# schematic.net
KiCad netlist of a schematic drawn in EAGLE
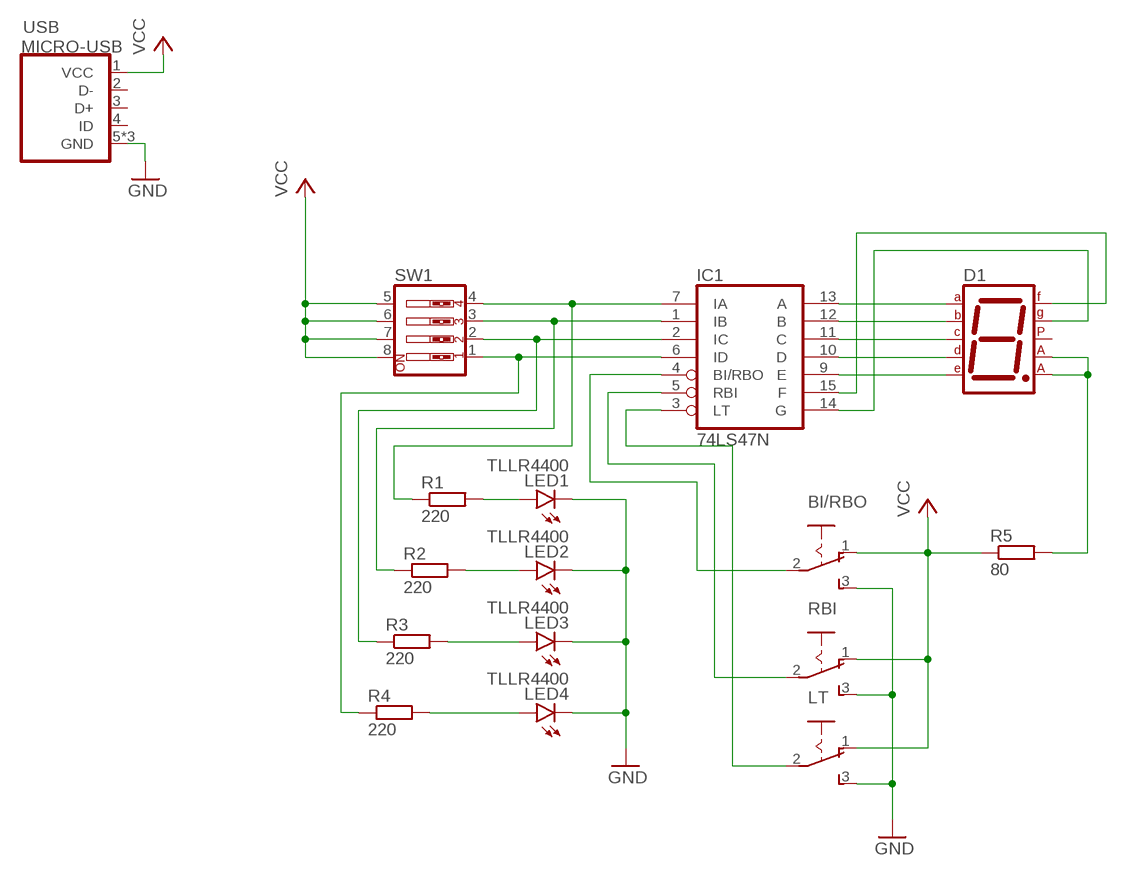
[diagram p0: schematic, sheet 1]

(export (version "E")
  (design (tool "Eeschema 10.0.6"))
  (components
    (comp (ref "BI/RBO")
      (value "255SB")
      (footprint "eagle-import:255SB")
      (libsource (lib "eagle-import") (part "255SB"))
    )
    (comp (ref "D1")
      (value "7SEG-CA")
      (footprint "eagle-import:7SEG-13")
      (libsource (lib "eagle-import") (part "7SEG-CA"))
    )
    (comp (ref "IC1")
      (value "74LS47N")
      (footprint "eagle-import:DIL16")
      (libsource (lib "eagle-import") (part "7447NLS"))
    )
    (comp (ref "LED1")
      (value "TLLR4400")
      (footprint "eagle-import:LED3MM")
      (fields (field (name "MF") "VISHAY SEMICONDUCTOR"))
      (libsource (lib "eagle-import") (part "TLLR4400"))
    )
    (comp (ref "LED2")
      (value "TLLR4400")
      (footprint "eagle-import:LED3MM")
      (fields (field (name "MF") "VISHAY SEMICONDUCTOR"))
      (libsource (lib "eagle-import") (part "TLLR4400"))
    )
    (comp (ref "LED3")
      (value "TLLR4400")
      (footprint "eagle-import:LED3MM")
      (fields (field (name "MF") "VISHAY SEMICONDUCTOR"))
      (libsource (lib "eagle-import") (part "TLLR4400"))
    )
    (comp (ref "LED4")
      (value "TLLR4400")
      (footprint "eagle-import:LED3MM")
      (fields (field (name "MF") "VISHAY SEMICONDUCTOR"))
      (libsource (lib "eagle-import") (part "TLLR4400"))
    )
    (comp (ref "LT")
      (value "255SB")
      (footprint "eagle-import:255SB")
      (libsource (lib "eagle-import") (part "255SB"))
    )
    (comp (ref "R1")
      (value "220")
      (footprint "eagle-import:0207_10")
      (libsource (lib "eagle-import") (part "R-EU_0207/10"))
    )
    (comp (ref "R2")
      (value "220")
      (footprint "eagle-import:0207_10")
      (libsource (lib "eagle-import") (part "R-EU_0207/10"))
    )
    (comp (ref "R3")
      (value "220")
      (footprint "eagle-import:0207_10")
      (libsource (lib "eagle-import") (part "R-EU_0207/10"))
    )
    (comp (ref "R4")
      (value "220")
      (footprint "eagle-import:0207_10")
      (libsource (lib "eagle-import") (part "R-EU_0207/10"))
    )
    (comp (ref "R5")
      (value "80")
      (footprint "eagle-import:0207_10")
      (libsource (lib "eagle-import") (part "R-EU_0207/10"))
    )
    (comp (ref "RBI")
      (value "255SB")
      (footprint "eagle-import:255SB")
      (libsource (lib "eagle-import") (part "255SB"))
    )
    (comp (ref "SW1")
      (value "SW_DIP-4")
      (footprint "eagle-import:EDG-04")
      (libsource (lib "eagle-import") (part "SW_DIP-4"))
    )
    (comp (ref "USB")
      (value "MICRO-USB")
      (footprint "eagle-import:MICRO-USB")
      (libsource (lib "eagle-import") (part "MICRO-USB"))
    )
  )
  (nets
    (net (code "1") (name "GND") (class "Default")
      (node (ref "BI/RBO") (pin "3") (pinfunction "S_3") (pintype "passive"))
      (node (ref "LED1") (pin "K") (pinfunction "C_K") (pintype "passive"))
      (node (ref "LED2") (pin "K") (pinfunction "C_K") (pintype "passive"))
      (node (ref "LED3") (pin "K") (pinfunction "C_K") (pintype "passive"))
      (node (ref "LED4") (pin "K") (pinfunction "C_K") (pintype "passive"))
      (node (ref "LT") (pin "3") (pinfunction "S_3") (pintype "passive"))
      (node (ref "RBI") (pin "3") (pinfunction "S_3") (pintype "passive"))
      (node (ref "USB") (pin "5") (pinfunction "GND_5") (pintype "power_in"))
      (node (ref "USB") (pin "GND1") (pinfunction "GND_GND1") (pintype "power_in"))
      (node (ref "USB") (pin "GND2") (pinfunction "GND_GND2") (pintype "power_in"))
    )
    (net (code "2") (name "Net-(BI/RBO-P)") (class "Default")
      (node (ref "BI/RBO") (pin "2") (pinfunction "P_2") (pintype "passive"))
      (node (ref "IC1") (pin "4") (pinfunction "BI/RBO_4") (pintype "input"))
    )
    (net (code "3") (name "Net-(D1-A)") (class "Default")
      (node (ref "D1") (pin "7") (pinfunction "A_7") (pintype "passive"))
      (node (ref "IC1") (pin "13") (pinfunction "A_13") (pintype "output"))
    )
    (net (code "4") (name "Net-(D1-B)") (class "Default")
      (node (ref "D1") (pin "6") (pinfunction "B_6") (pintype "passive"))
      (node (ref "IC1") (pin "12") (pinfunction "B_12") (pintype "output"))
    )
    (net (code "5") (name "Net-(D1-C)") (class "Default")
      (node (ref "D1") (pin "4") (pinfunction "C_4") (pintype "passive"))
      (node (ref "IC1") (pin "11") (pinfunction "C_11") (pintype "output"))
    )
    (net (code "6") (name "Net-(D1-CA1)") (class "Default")
      (node (ref "D1") (pin "3") (pinfunction "CA1_3") (pintype "passive"))
      (node (ref "D1") (pin "8") (pinfunction "CA2_8") (pintype "passive"))
      (node (ref "R5") (pin "2") (pinfunction "2_2") (pintype "passive"))
    )
    (net (code "7") (name "Net-(D1-D)") (class "Default")
      (node (ref "D1") (pin "2") (pinfunction "D_2") (pintype "passive"))
      (node (ref "IC1") (pin "10") (pinfunction "D_10") (pintype "output"))
    )
    (net (code "8") (name "Net-(D1-E)") (class "Default")
      (node (ref "D1") (pin "1") (pinfunction "E_1") (pintype "passive"))
      (node (ref "IC1") (pin "9") (pinfunction "E_9") (pintype "output"))
    )
    (net (code "9") (name "Net-(D1-F)") (class "Default")
      (node (ref "D1") (pin "9") (pinfunction "F_9") (pintype "passive"))
      (node (ref "IC1") (pin "15") (pinfunction "F_15") (pintype "output"))
    )
    (net (code "10") (name "Net-(D1-G)") (class "Default")
      (node (ref "D1") (pin "10") (pinfunction "G_10") (pintype "passive"))
      (node (ref "IC1") (pin "14") (pinfunction "G_14") (pintype "output"))
    )
    (net (code "11") (name "Net-(IC1A-IA)") (class "Default")
      (node (ref "IC1") (pin "7") (pinfunction "IA_7") (pintype "input"))
      (node (ref "R1") (pin "1") (pinfunction "1_1") (pintype "passive"))
      (node (ref "SW1") (pin "4") (pinfunction "4_4") (pintype "passive"))
    )
    (net (code "12") (name "Net-(IC1A-IB)") (class "Default")
      (node (ref "IC1") (pin "1") (pinfunction "IB_1") (pintype "input"))
      (node (ref "R2") (pin "1") (pinfunction "1_1") (pintype "passive"))
      (node (ref "SW1") (pin "3") (pinfunction "3_3") (pintype "passive"))
    )
    (net (code "13") (name "Net-(IC1A-IC)") (class "Default")
      (node (ref "IC1") (pin "2") (pinfunction "IC_2") (pintype "input"))
      (node (ref "R3") (pin "1") (pinfunction "1_1") (pintype "passive"))
      (node (ref "SW1") (pin "2") (pinfunction "2_2") (pintype "passive"))
    )
    (net (code "14") (name "Net-(IC1A-ID)") (class "Default")
      (node (ref "IC1") (pin "6") (pinfunction "ID_6") (pintype "input"))
      (node (ref "R4") (pin "1") (pinfunction "1_1") (pintype "passive"))
      (node (ref "SW1") (pin "1") (pinfunction "1_1") (pintype "passive"))
    )
    (net (code "15") (name "Net-(IC1A-LT)") (class "Default")
      (node (ref "IC1") (pin "3") (pinfunction "LT_3") (pintype "input"))
      (node (ref "LT") (pin "2") (pinfunction "P_2") (pintype "passive"))
    )
    (net (code "16") (name "Net-(IC1A-RBI)") (class "Default")
      (node (ref "IC1") (pin "5") (pinfunction "RBI_5") (pintype "input"))
      (node (ref "RBI") (pin "2") (pinfunction "P_2") (pintype "passive"))
    )
    (net (code "17") (name "Net-(LED1-PadA)") (class "Default")
      (node (ref "LED1") (pin "A") (pinfunction "A_A") (pintype "passive"))
      (node (ref "R1") (pin "2") (pinfunction "2_2") (pintype "passive"))
    )
    (net (code "18") (name "Net-(LED2-PadA)") (class "Default")
      (node (ref "LED2") (pin "A") (pinfunction "A_A") (pintype "passive"))
      (node (ref "R2") (pin "2") (pinfunction "2_2") (pintype "passive"))
    )
    (net (code "19") (name "Net-(LED3-PadA)") (class "Default")
      (node (ref "LED3") (pin "A") (pinfunction "A_A") (pintype "passive"))
      (node (ref "R3") (pin "2") (pinfunction "2_2") (pintype "passive"))
    )
    (net (code "20") (name "Net-(LED4-PadA)") (class "Default")
      (node (ref "LED4") (pin "A") (pinfunction "A_A") (pintype "passive"))
      (node (ref "R4") (pin "2") (pinfunction "2_2") (pintype "passive"))
    )
    (net (code "21") (name "VCC") (class "Default")
      (node (ref "BI/RBO") (pin "1") (pinfunction "O_1") (pintype "passive"))
      (node (ref "LT") (pin "1") (pinfunction "O_1") (pintype "passive"))
      (node (ref "R5") (pin "1") (pinfunction "1_1") (pintype "passive"))
      (node (ref "RBI") (pin "1") (pinfunction "O_1") (pintype "passive"))
      (node (ref "SW1") (pin "5") (pinfunction "5_5") (pintype "passive"))
      (node (ref "SW1") (pin "6") (pinfunction "6_6") (pintype "passive"))
      (node (ref "SW1") (pin "7") (pinfunction "7_7") (pintype "passive"))
      (node (ref "SW1") (pin "8") (pinfunction "8_8") (pintype "passive"))
      (node (ref "USB") (pin "1") (pinfunction "VCC_1") (pintype "power_in"))
    )
    (net (code "22") (name "unconnected-(D1-DP-Pad5)") (class "Default")
      (node (ref "D1") (pin "5") (pinfunction "DP_5") (pintype "passive"))
    )
    (net (code "23") (name "unconnected-(USB-D+-Pad3)") (class "Default")
      (node (ref "USB") (pin "3") (pinfunction "D+_3") (pintype "bidirectional"))
    )
    (net (code "24") (name "unconnected-(USB-D--Pad2)") (class "Default")
      (node (ref "USB") (pin "2") (pinfunction "D-_2") (pintype "bidirectional"))
    )
    (net (code "25") (name "unconnected-(USB-ID-Pad4)") (class "Default")
      (node (ref "USB") (pin "4") (pinfunction "ID_4") (pintype "bidirectional"))
    )
  )
)
